# Sheet2.net
KiCad netlist of a schematic drawn in Altium Designer
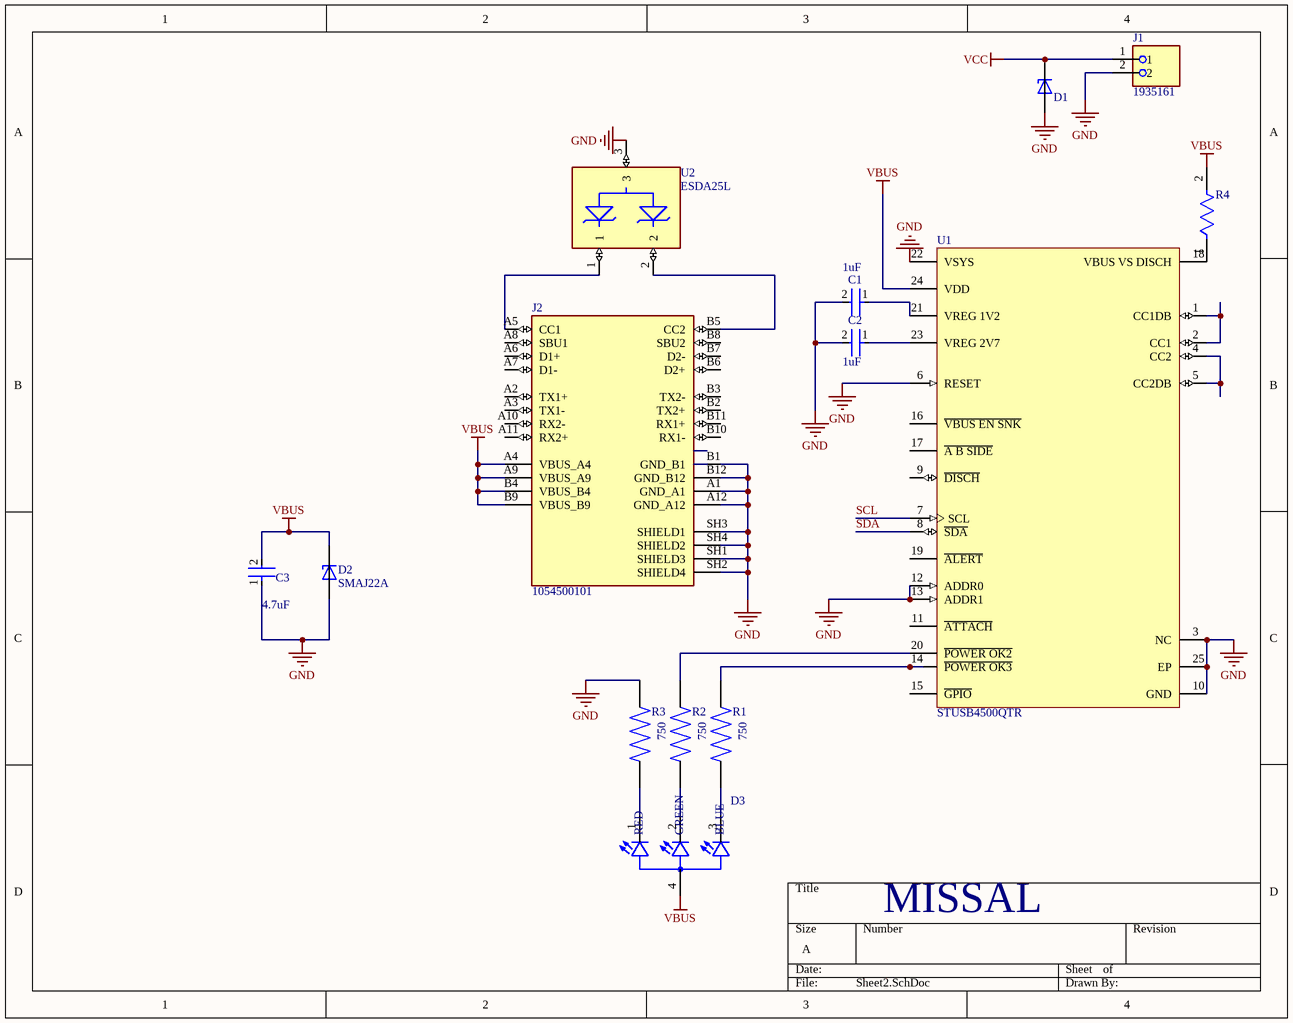
[diagram p0: Sheet2.SchDoc]

(export (version "E")
  (design (tool "Eeschema 10.0.6"))
  (components
    (comp (ref "C1")
      (value "CL10B105KP8NNNC")
      (footprint "FP-CL10-IPC_C")
      (description "Cap Ceramic 1uF 10V X7R ±10% Pad SMD 0603 +125°C T/R")
      (fields (field (name "CAPACITANCE") "1uF") (field (name "TOLERANCE") "10%"))
      (libsource (lib "Altium Content Vault") (part "b4654b650e69147ec39a6b967a45e02"))
    )
    (comp (ref "C2")
      (value "CL10B105KP8NNNC")
      (footprint "FP-CL10-IPC_C")
      (description "Cap Ceramic 1uF 10V X7R ±10% Pad SMD 0603 +125°C T/R")
      (fields (field (name "CAPACITANCE") "1uF") (field (name "TOLERANCE") "10%"))
      (libsource (lib "Altium Content Vault") (part "b4654b650e69147ec39a6b967a45e02"))
    )
    (comp (ref "C3")
      (value "GRM188R61E475KE11D")
      (footprint "FP-GRM188-0_15-IPC_C")
      (description "Chip Multilayer Ceramic Capacitors for General Purpose, 0603, 4.7uF, X5R, 15%, 10%, 25V")
      (fields
        (field (name "CAPACITANCE") "4.7uF")
        (field (name "VOLTAGE") "25V")
        (field (name "TOLERANCE") "10%")
      )
      (libsource (lib "Altium Content Vault") (part "02cd4be3c70576c341d710602a673aa"))
    )
    (comp (ref "D1")
      (value "SMAJ22A")
      (footprint "DIOM4325X250N")
      (description "SMAJ Series 35.5 V 0.4 kW Surface Mount Uni-Directional TVS Diode - DO-214AC")
      (fields (field (name "MF") "Littelfuse"))
      (libsource (lib "SMAJ22A") (part "SMAJ22A"))
    )
    (comp (ref "D2")
      (value "SMAJ22A")
      (footprint "DIOM4325X250N")
      (description "SMAJ Series 35.5 V 0.4 kW Surface Mount Uni-Directional TVS Diode - DO-214AC")
      (fields (field (name "MF") "Littelfuse"))
      (libsource (lib "SMAJ22A") (part "SMAJ22A"))
    )
    (comp (ref "D3")
      (value "19-237/R6GHBHC-A01/2T")
      (footprint "LED_19-237/R6GHBHC-A01/2T")
      (fields (field (name "MF") "Everlight Electronics"))
      (libsource (lib "19-237_R6GHBHC-A01_2T") (part "19-237/R6GHBHC-A01/2T"))
    )
    (comp (ref "J1")
      (value "1935161")
      (footprint "PHOENIX_1935161")
      (fields (field (name "MF") "{'manufacturer': u'Phoenix Contact'}"))
      (libsource (lib "1935161") (part "1935161"))
    )
    (comp (ref "J2")
      (value "1054500101")
      (footprint "MOLEX_1054500101")
      (fields (field (name "MF") "Molex"))
      (libsource (lib "1054500101") (part "1054500101"))
    )
    (comp (ref "R1")
      (value "750")
      (footprint "RES_ERJP06J751V")
      (fields (field (name "MP") "ERJP06J751V"))
      (libsource (lib "ERJP06J751V") (part "ERJP06J751V"))
    )
    (comp (ref "R2")
      (value "750")
      (footprint "RES_ERJP06J751V")
      (fields (field (name "MP") "ERJP06J751V"))
      (libsource (lib "ERJP06J751V") (part "ERJP06J751V"))
    )
    (comp (ref "R3")
      (value "750")
      (footprint "RES_ERJP06J751V")
      (fields (field (name "MP") "ERJP06J751V"))
      (libsource (lib "ERJP06J751V") (part "ERJP06J751V"))
    )
    (comp (ref "R4")
      (value "RMCF0603FG1K00")
      (footprint "FP-RMCF0603-IPC_B")
      (description "1kΩ ±1% 0.1W 0603 Thick Film Chip Resistor AEC-Q200 compliant")
      (fields (field (name "TOLERANCE") "1%"))
      (libsource (lib "Altium Content Vault") (part "1029c3af85768c4190bb7ad29bc67b5"))
    )
    (comp (ref "U1")
      (value "STUSB4500QTR")
      (footprint "FP-QFN-24-EP_4x4-MFG")
      (description "4.1V~22V USB 2.0 I2C Controllers Interface ICs STUSB45 Controller 24-VFQFN Exposed Pad")
      (libsource (lib "Altium Content Vault") (part "STUSB4500QTR"))
    )
    (comp (ref "U2")
      (value "ESDA25L")
      (footprint "SOT-23-3L")
      (description "- Clamp - Ipp Tvs Diode Surface Mount SOT-23-3")
      (fields (field (name "MF") "STMicroelectronics"))
      (libsource (lib "ESDA25L") (part "ESDA25L"))
    )
  )
  (nets
    (net (code "1") (name "/SCL") (class "Default")
      (node (ref "U1") (pin "7") (pinfunction "SCL_7") (pintype "input"))
    )
    (net (code "2") (name "/SDA") (class "Default")
      (node (ref "U1") (pin "8") (pinfunction "~{SDA}_8") (pintype "bidirectional"))
    )
    (net (code "3") (name "GND") (class "Default")
      (node (ref "C1") (pin "2") (pinfunction "2_2") (pintype "passive"))
      (node (ref "C2") (pin "2") (pinfunction "2_2") (pintype "passive"))
      (node (ref "C3") (pin "1") (pinfunction "1_1") (pintype "passive"))
      (node (ref "D1") (pin "A") (pinfunction "A_A") (pintype "passive"))
      (node (ref "D2") (pin "A") (pinfunction "A_A") (pintype "passive"))
      (node (ref "J1") (pin "2") (pinfunction "2_2") (pintype "passive"))
      (node (ref "J2") (pin "A1") (pinfunction "GND_A1_A1") (pintype "power_in"))
      (node (ref "J2") (pin "A12") (pinfunction "GND_A12_A12") (pintype "power_in"))
      (node (ref "J2") (pin "B1") (pinfunction "GND_B1_B1") (pintype "power_in"))
      (node (ref "J2") (pin "B12") (pinfunction "GND_B12_B12") (pintype "power_in"))
      (node (ref "J2") (pin "SH1") (pinfunction "SHIELD3_SH1") (pintype "passive"))
      (node (ref "J2") (pin "SH2") (pinfunction "SHIELD4_SH2") (pintype "passive"))
      (node (ref "J2") (pin "SH3") (pinfunction "SHIELD1_SH3") (pintype "passive"))
      (node (ref "J2") (pin "SH4") (pinfunction "SHIELD2_SH4") (pintype "passive"))
      (node (ref "R3") (pin "2") (pinfunction "2_2") (pintype "passive"))
      (node (ref "U1") (pin "10") (pinfunction "GND_10") (pintype "power_in"))
      (node (ref "U1") (pin "12") (pinfunction "ADDR0_12") (pintype "input"))
      (node (ref "U1") (pin "13") (pinfunction "ADDR1_13") (pintype "input"))
      (node (ref "U1") (pin "22") (pinfunction "VSYS_22") (pintype "power_in"))
      (node (ref "U1") (pin "25") (pinfunction "EP_25") (pintype "power_in"))
      (node (ref "U1") (pin "3") (pinfunction "NC_3") (pintype "passive"))
      (node (ref "U1") (pin "6") (pinfunction "RESET_6") (pintype "input"))
      (node (ref "U2") (pin "3") (pinfunction "3_3") (pintype "bidirectional"))
    )
    (net (code "4") (name "Net-(D3-B_C)") (class "Default")
      (node (ref "D3") (pin "3") (pinfunction "B_C_3") (pintype "passive"))
      (node (ref "R1") (pin "1") (pinfunction "1_1") (pintype "passive"))
    )
    (net (code "5") (name "Net-(D3-G_C)") (class "Default")
      (node (ref "D3") (pin "2") (pinfunction "G_C_2") (pintype "passive"))
      (node (ref "R2") (pin "1") (pinfunction "1_1") (pintype "passive"))
    )
    (net (code "6") (name "Net-(D3-R_C)") (class "Default")
      (node (ref "D3") (pin "1") (pinfunction "R_C_1") (pintype "passive"))
      (node (ref "R3") (pin "1") (pinfunction "1_1") (pintype "passive"))
    )
    (net (code "7") (name "Net-(J2-CC1)") (class "Default")
      (node (ref "J2") (pin "A5") (pinfunction "CC1_A5") (pintype "bidirectional"))
      (node (ref "U2") (pin "1") (pinfunction "1_1") (pintype "bidirectional"))
    )
    (net (code "8") (name "Net-(J2-CC2)") (class "Default")
      (node (ref "J2") (pin "B5") (pinfunction "CC2_B5") (pintype "bidirectional"))
      (node (ref "U2") (pin "2") (pinfunction "2_2") (pintype "bidirectional"))
    )
    (net (code "9") (name "Net-(U1-CC1)") (class "Default")
      (node (ref "U1") (pin "1") (pinfunction "CC1DB_1") (pintype "bidirectional"))
      (node (ref "U1") (pin "2") (pinfunction "CC1_2") (pintype "bidirectional"))
    )
    (net (code "10") (name "Net-(U1-CC2)") (class "Default")
      (node (ref "U1") (pin "4") (pinfunction "CC2_4") (pintype "bidirectional"))
      (node (ref "U1") (pin "5") (pinfunction "CC2DB_5") (pintype "bidirectional"))
    )
    (net (code "11") (name "Net-(U1-VBUS_VS_DISCH)") (class "Default")
      (node (ref "R4") (pin "1") (pinfunction "1_1") (pintype "passive"))
      (node (ref "U1") (pin "18") (pinfunction "VBUS_VS_DISCH_18") (pintype "power_in"))
    )
    (net (code "12") (name "Net-(U1-VREG_1V2)") (class "Default")
      (node (ref "C1") (pin "1") (pinfunction "1_1") (pintype "passive"))
      (node (ref "U1") (pin "21") (pinfunction "VREG_1V2_21") (pintype "power_in"))
    )
    (net (code "13") (name "Net-(U1-VREG_2V7)") (class "Default")
      (node (ref "C2") (pin "1") (pinfunction "1_1") (pintype "passive"))
      (node (ref "U1") (pin "23") (pinfunction "VREG_2V7_23") (pintype "power_in"))
    )
    (net (code "14") (name "Net-(U1-~{POWER_OK2})") (class "Default")
      (node (ref "R2") (pin "2") (pinfunction "2_2") (pintype "passive"))
      (node (ref "U1") (pin "20") (pinfunction "~{POWER_OK2}_20") (pintype "power_in"))
    )
    (net (code "15") (name "Net-(U1-~{POWER_OK3})") (class "Default")
      (node (ref "R1") (pin "2") (pinfunction "2_2") (pintype "passive"))
      (node (ref "U1") (pin "14") (pinfunction "~{POWER_OK3}_14") (pintype "open_collector"))
    )
    (net (code "16") (name "VBUS") (class "Default")
      (node (ref "C3") (pin "2") (pinfunction "2_2") (pintype "passive"))
      (node (ref "D2") (pin "C") (pinfunction "C_C") (pintype "passive"))
      (node (ref "D3") (pin "4") (pinfunction "A_4") (pintype "passive"))
      (node (ref "J2") (pin "A4") (pinfunction "VBUS_A4_A4") (pintype "power_in"))
      (node (ref "J2") (pin "A9") (pinfunction "VBUS_A9_A9") (pintype "power_in"))
      (node (ref "J2") (pin "B4") (pinfunction "VBUS_B4_B4") (pintype "power_in"))
      (node (ref "J2") (pin "B9") (pinfunction "VBUS_B9_B9") (pintype "power_in"))
      (node (ref "R4") (pin "2") (pinfunction "2_2") (pintype "passive"))
      (node (ref "U1") (pin "24") (pinfunction "VDD_24") (pintype "power_in"))
    )
    (net (code "17") (name "VCC") (class "Default")
      (node (ref "D1") (pin "C") (pinfunction "C_C") (pintype "passive"))
      (node (ref "J1") (pin "1") (pinfunction "1_1") (pintype "passive"))
    )
    (net (code "18") (name "unconnected-(J2-D1+-PadA6)") (class "Default")
      (node (ref "J2") (pin "A6") (pinfunction "D1+_A6") (pintype "bidirectional"))
    )
    (net (code "19") (name "unconnected-(J2-D1--PadA7)") (class "Default")
      (node (ref "J2") (pin "A7") (pinfunction "D1-_A7") (pintype "bidirectional"))
    )
    (net (code "20") (name "unconnected-(J2-D2+-PadB6)") (class "Default")
      (node (ref "J2") (pin "B6") (pinfunction "D2+_B6") (pintype "bidirectional"))
    )
    (net (code "21") (name "unconnected-(J2-D2--PadB7)") (class "Default")
      (node (ref "J2") (pin "B7") (pinfunction "D2-_B7") (pintype "bidirectional"))
    )
    (net (code "22") (name "unconnected-(J2-RX1+-PadB11)") (class "Default")
      (node (ref "J2") (pin "B11") (pinfunction "RX1+_B11") (pintype "bidirectional"))
    )
    (net (code "23") (name "unconnected-(J2-RX1--PadB10)") (class "Default")
      (node (ref "J2") (pin "B10") (pinfunction "RX1-_B10") (pintype "bidirectional"))
    )
    (net (code "24") (name "unconnected-(J2-RX2+-PadA11)") (class "Default")
      (node (ref "J2") (pin "A11") (pinfunction "RX2+_A11") (pintype "bidirectional"))
    )
    (net (code "25") (name "unconnected-(J2-RX2--PadA10)") (class "Default")
      (node (ref "J2") (pin "A10") (pinfunction "RX2-_A10") (pintype "bidirectional"))
    )
    (net (code "26") (name "unconnected-(J2-SBU1-PadA8)") (class "Default")
      (node (ref "J2") (pin "A8") (pinfunction "SBU1_A8") (pintype "bidirectional"))
    )
    (net (code "27") (name "unconnected-(J2-SBU2-PadB8)") (class "Default")
      (node (ref "J2") (pin "B8") (pinfunction "SBU2_B8") (pintype "bidirectional"))
    )
    (net (code "28") (name "unconnected-(J2-TX1+-PadA2)") (class "Default")
      (node (ref "J2") (pin "A2") (pinfunction "TX1+_A2") (pintype "bidirectional"))
    )
    (net (code "29") (name "unconnected-(J2-TX1--PadA3)") (class "Default")
      (node (ref "J2") (pin "A3") (pinfunction "TX1-_A3") (pintype "bidirectional"))
    )
    (net (code "30") (name "unconnected-(J2-TX2+-PadB2)") (class "Default")
      (node (ref "J2") (pin "B2") (pinfunction "TX2+_B2") (pintype "bidirectional"))
    )
    (net (code "31") (name "unconnected-(J2-TX2--PadB3)") (class "Default")
      (node (ref "J2") (pin "B3") (pinfunction "TX2-_B3") (pintype "bidirectional"))
    )
    (net (code "32") (name "unconnected-(U1-~{ALERT}-Pad19)") (class "Default")
      (node (ref "U1") (pin "19") (pinfunction "~{ALERT}_19") (pintype "open_collector"))
    )
    (net (code "33") (name "unconnected-(U1-~{ATTACH}-Pad11)") (class "Default")
      (node (ref "U1") (pin "11") (pinfunction "~{ATTACH}_11") (pintype "open_collector"))
    )
    (net (code "34") (name "unconnected-(U1-~{A_B_SIDE}-Pad17)") (class "Default")
      (node (ref "U1") (pin "17") (pinfunction "~{A_B_SIDE}_17") (pintype "open_collector"))
    )
    (net (code "35") (name "unconnected-(U1-~{DISCH}-Pad9)") (class "Default")
      (node (ref "U1") (pin "9") (pinfunction "~{DISCH}_9") (pintype "bidirectional"))
    )
    (net (code "36") (name "unconnected-(U1-~{GPIO}-Pad15)") (class "Default")
      (node (ref "U1") (pin "15") (pinfunction "~{GPIO}_15") (pintype "open_collector"))
    )
    (net (code "37") (name "unconnected-(U1-~{VBUS_EN_SNK}-Pad16)") (class "Default")
      (node (ref "U1") (pin "16") (pinfunction "~{VBUS_EN_SNK}_16") (pintype "open_collector"))
    )
  )
)
